# NotNightVision_r002.net
KiCad netlist of a schematic drawn in EAGLE
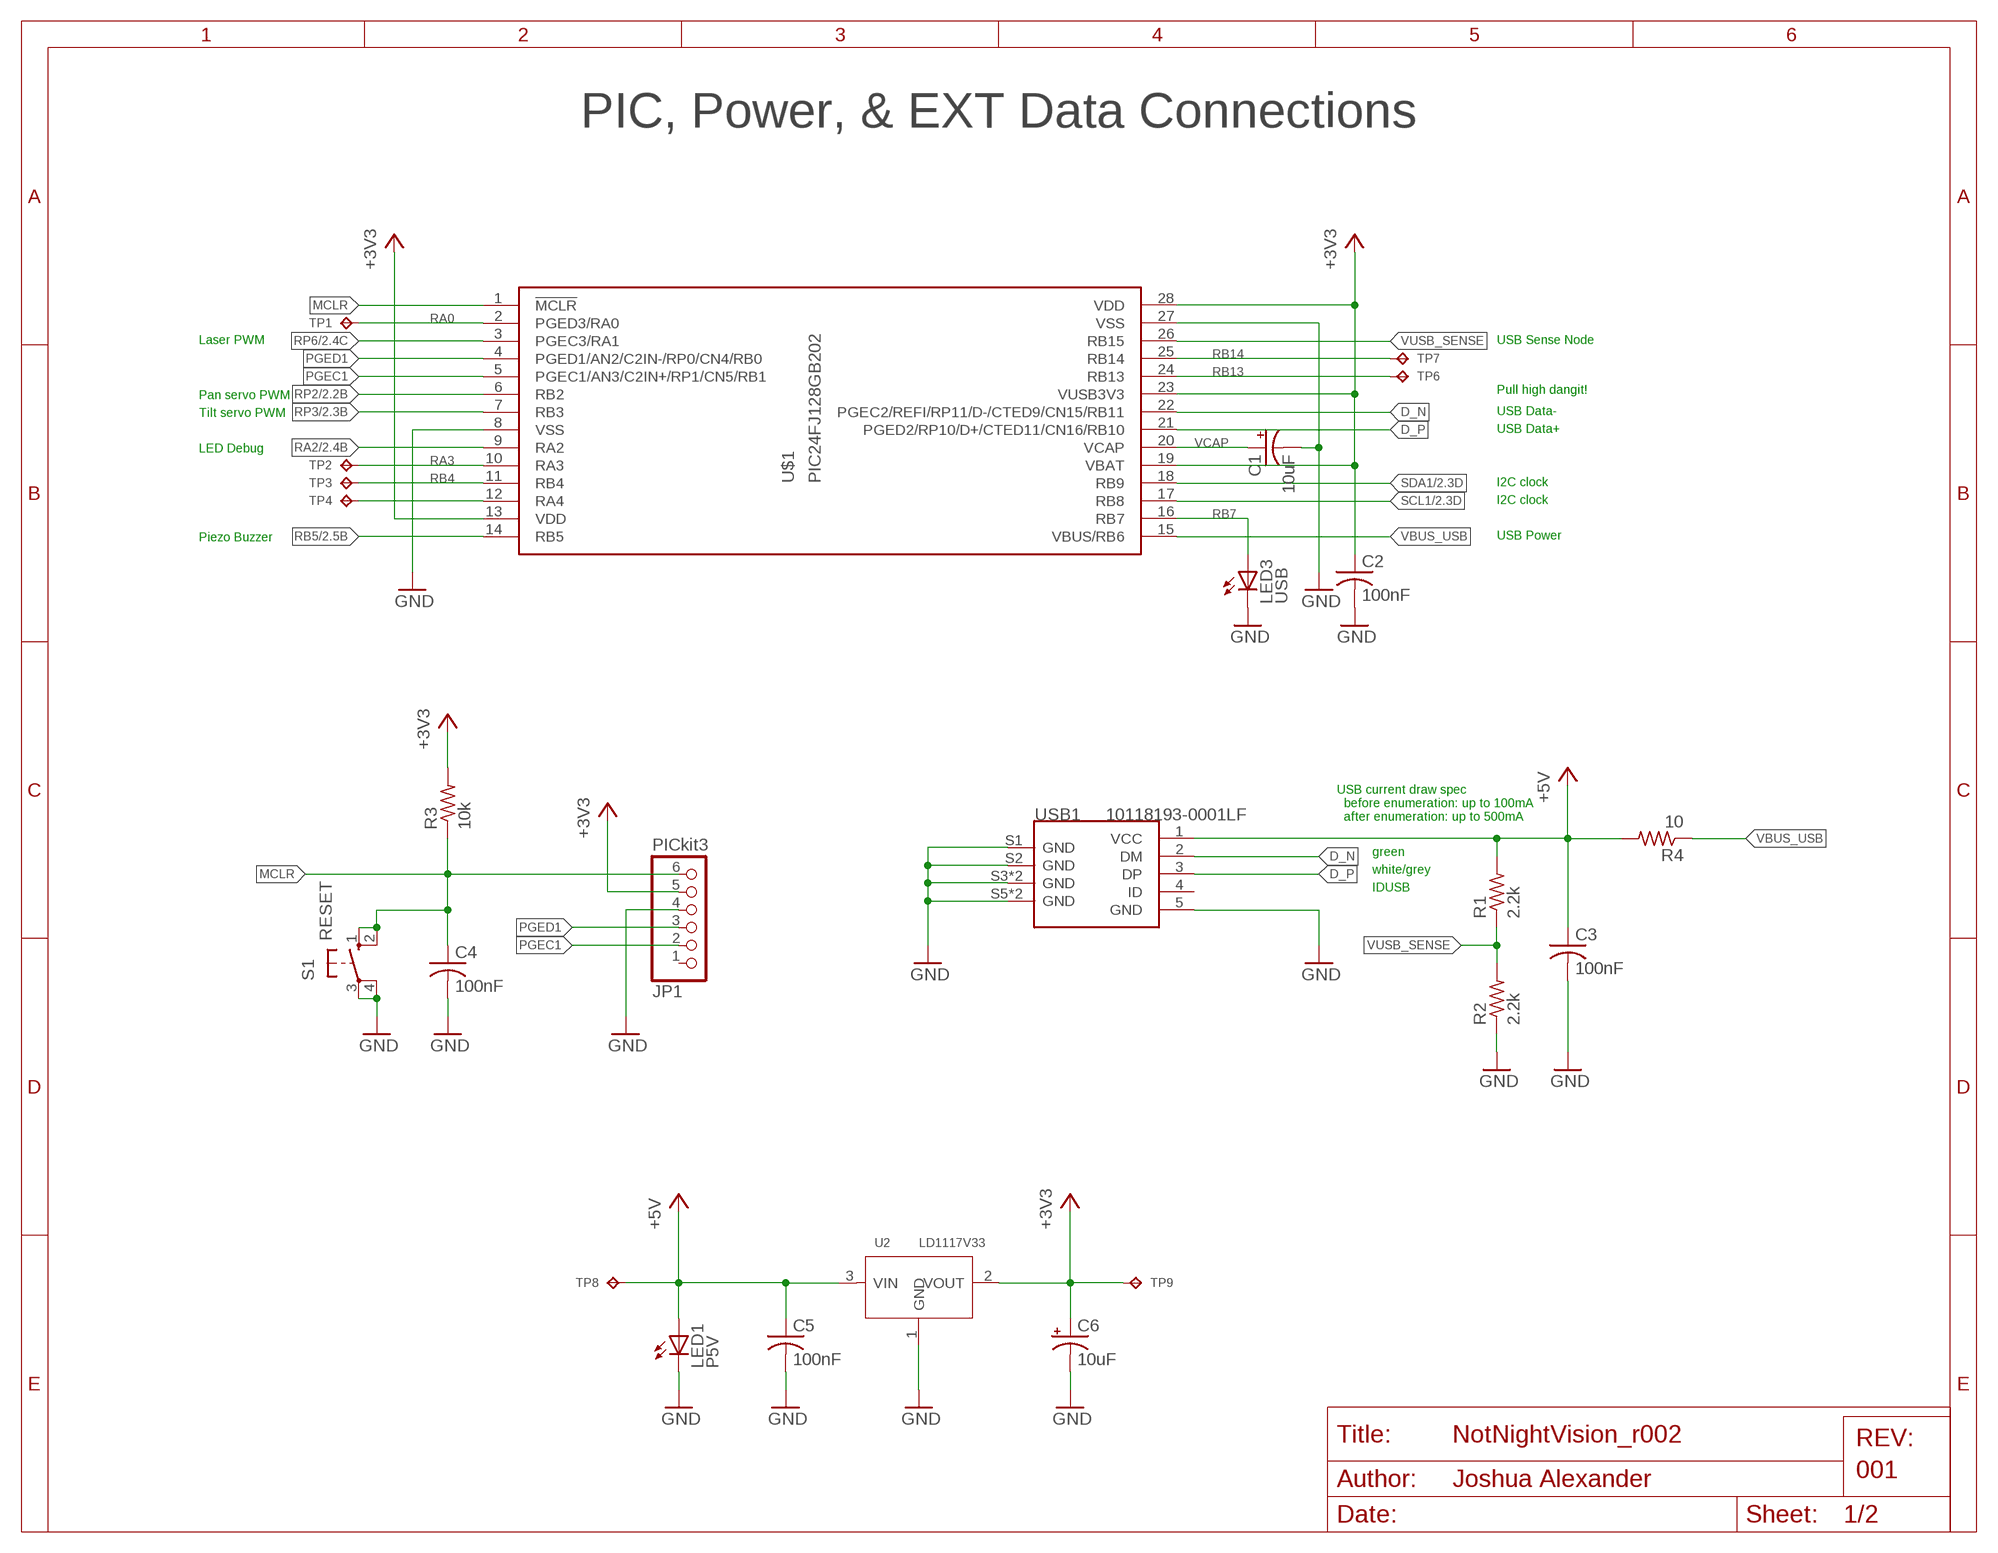
[diagram p0: schematic, sheet 1]
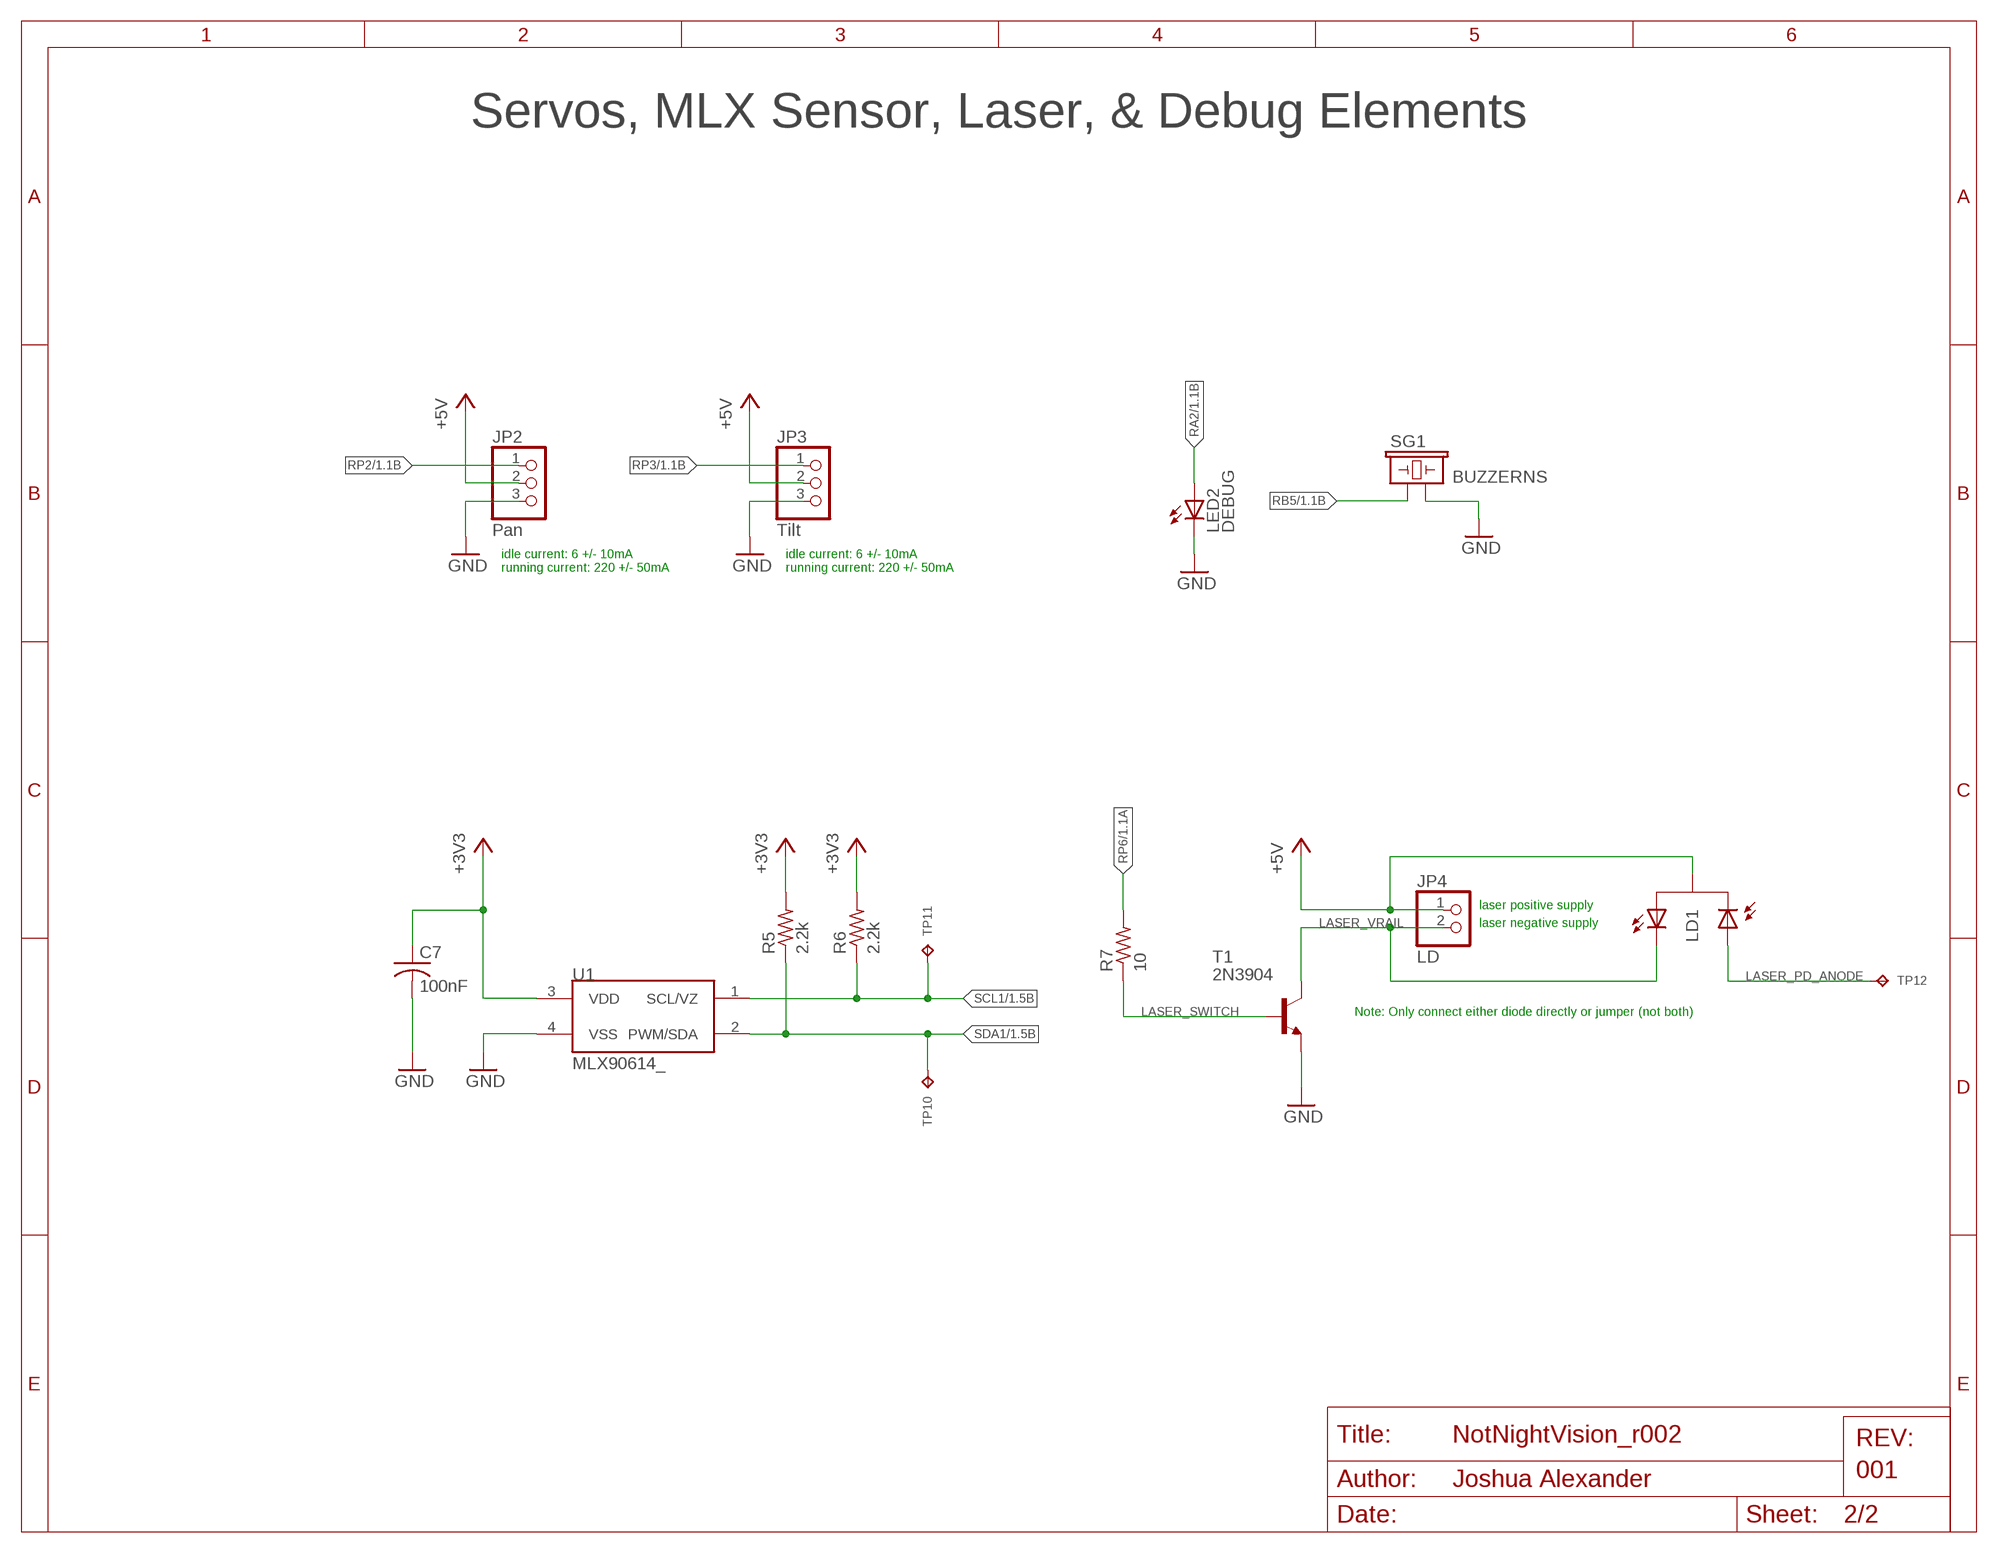
[diagram p1: schematic, sheet 2]

(export (version "E")
  (design (tool "Eeschema 10.0.6"))
  (components
    (comp (ref "C7")
      (value "100nF")
      (footprint "eagle-import:C050-030X075")
      (libsource (lib "eagle-import") (part "C-US050-030X075"))
    )
    (comp (ref "JP2")
      (value "Pan")
      (footprint "eagle-import:1X03")
      (libsource (lib "eagle-import") (part "PINHD-1X3"))
    )
    (comp (ref "JP3")
      (value "Tilt")
      (footprint "eagle-import:1X03")
      (libsource (lib "eagle-import") (part "PINHD-1X3"))
    )
    (comp (ref "JP4")
      (value "LD")
      (footprint "eagle-import:1X02")
      (libsource (lib "eagle-import") (part "PINHD-1X2"))
    )
    (comp (ref "LD1")
      (value "LASER_DIODE")
      (footprint "eagle-import:TO-18")
      (libsource (lib "eagle-import") (part "LASER_DIODE"))
    )
    (comp (ref "LED2")
      (value "DEBUG")
      (footprint "eagle-import:LED3MM")
      (libsource (lib "eagle-import") (part "LED3MM"))
    )
    (comp (ref "R5")
      (value "2.2k")
      (footprint "eagle-import:0207_7")
      (libsource (lib "eagle-import") (part "R-US_0207/7"))
    )
    (comp (ref "R6")
      (value "2.2k")
      (footprint "eagle-import:0207_7")
      (libsource (lib "eagle-import") (part "R-US_0207/7"))
    )
    (comp (ref "R7")
      (value "10")
      (footprint "eagle-import:0207_7")
      (libsource (lib "eagle-import") (part "R-US_0207/7"))
    )
    (comp (ref "SG1")
      (value "BUZZERNS")
      (footprint "eagle-import:BUZZER-12MM-NS")
      (libsource (lib "eagle-import") (part "BUZZERNS"))
    )
    (comp (ref "T1")
      (value "2N3904")
      (footprint "eagle-import:TO92")
      (libsource (lib "eagle-import") (part "2N3904"))
    )
    (comp (ref "TP10")
      (value "TP10")
      (footprint "eagle-import:10MIL_ROUND")
      (libsource (lib "eagle-import") (part "TP10"))
    )
    (comp (ref "TP11")
      (value "TP10")
      (footprint "eagle-import:10MIL_ROUND")
      (libsource (lib "eagle-import") (part "TP10"))
    )
    (comp (ref "TP12")
      (value "TP10")
      (footprint "eagle-import:10MIL_ROUND")
      (libsource (lib "eagle-import") (part "TP10"))
    )
    (comp (ref "U1")
      (value "MLX90614_")
      (footprint "eagle-import:TO-39")
      (fields (field (name "MPN") "1747"))
      (libsource (lib "eagle-import") (part "MLX90614_"))
    )
    (comp (ref "C1")
      (value "10uF")
      (footprint "eagle-import:E2,5-7")
      (libsource (lib "eagle-import") (part "CPOL-USE2.5-7"))
    )
    (comp (ref "C2")
      (value "100nF")
      (footprint "eagle-import:C050-030X075")
      (libsource (lib "eagle-import") (part "C-US050-030X075"))
    )
    (comp (ref "C3")
      (value "100nF")
      (footprint "eagle-import:C050-030X075")
      (libsource (lib "eagle-import") (part "C-US050-030X075"))
    )
    (comp (ref "C4")
      (value "100nF")
      (footprint "eagle-import:C050-030X075")
      (libsource (lib "eagle-import") (part "C-US050-030X075"))
    )
    (comp (ref "C5")
      (value "100nF")
      (footprint "eagle-import:C050-030X075")
      (libsource (lib "eagle-import") (part "C-US050-030X075"))
    )
    (comp (ref "C6")
      (value "10uF")
      (footprint "eagle-import:E2,5-7")
      (libsource (lib "eagle-import") (part "CPOL-USE2.5-7"))
    )
    (comp (ref "JP1")
      (value "PICkit3")
      (footprint "eagle-import:1X06_90")
      (libsource (lib "eagle-import") (part "PINHD-1X6/90"))
    )
    (comp (ref "LED1")
      (value "P5V")
      (footprint "eagle-import:LED5MM")
      (libsource (lib "eagle-import") (part "LED5MM"))
    )
    (comp (ref "LED3")
      (value "USB")
      (footprint "eagle-import:LED3MM")
      (libsource (lib "eagle-import") (part "LED3MM"))
    )
    (comp (ref "R1")
      (value "2.2k")
      (footprint "eagle-import:0207_7")
      (libsource (lib "eagle-import") (part "R-US_0207/7"))
    )
    (comp (ref "R2")
      (value "2.2k")
      (footprint "eagle-import:0207_7")
      (libsource (lib "eagle-import") (part "R-US_0207/7"))
    )
    (comp (ref "R3")
      (value "10k")
      (footprint "eagle-import:0207_7")
      (libsource (lib "eagle-import") (part "R-US_0207/7"))
    )
    (comp (ref "R4")
      (value "10")
      (footprint "eagle-import:0207_7")
      (libsource (lib "eagle-import") (part "R-US_0207/7"))
    )
    (comp (ref "S1")
      (value "RESET")
      (footprint "eagle-import:B3F-10XX")
      (fields (field (name "MPN") "B3F-1000"))
      (libsource (lib "eagle-import") (part "10-XX"))
    )
    (comp (ref "TP1")
      (value "TP10")
      (footprint "eagle-import:10MIL_ROUND")
      (libsource (lib "eagle-import") (part "TP10"))
    )
    (comp (ref "TP2")
      (value "TP10")
      (footprint "eagle-import:10MIL_ROUND")
      (libsource (lib "eagle-import") (part "TP10"))
    )
    (comp (ref "TP3")
      (value "TP10")
      (footprint "eagle-import:10MIL_ROUND")
      (libsource (lib "eagle-import") (part "TP10"))
    )
    (comp (ref "TP4")
      (value "TP10")
      (footprint "eagle-import:10MIL_ROUND")
      (libsource (lib "eagle-import") (part "TP10"))
    )
    (comp (ref "TP6")
      (value "TP10")
      (footprint "eagle-import:10MIL_ROUND")
      (libsource (lib "eagle-import") (part "TP10"))
    )
    (comp (ref "TP7")
      (value "TP10")
      (footprint "eagle-import:10MIL_ROUND")
      (libsource (lib "eagle-import") (part "TP10"))
    )
    (comp (ref "TP8")
      (value "TP10")
      (footprint "eagle-import:10MIL_ROUND")
      (libsource (lib "eagle-import") (part "TP10"))
    )
    (comp (ref "TP9")
      (value "TP10")
      (footprint "eagle-import:10MIL_ROUND")
      (libsource (lib "eagle-import") (part "TP10"))
    )
    (comp (ref "U$1")
      (value "PIC24FJ128GB202")
      (footprint "eagle-import:DIL28-3")
      (libsource (lib "eagle-import") (part "PIC24FJ128GB202"))
    )
    (comp (ref "U2")
      (value "LD1117V33")
      (footprint "eagle-import:TO-220V")
      (libsource (lib "eagle-import") (part "LD1117V33TO220V"))
    )
    (comp (ref "USB1")
      (value "10118193-0001LF")
      (footprint "eagle-import:MICRO-USB5+6P-SMD-0.65-B")
      (libsource (lib "eagle-import") (part "MICRO-USB-SMD-B-(10118193-0001LF)"))
    )
  )
  (nets
    (net (code "1") (name "+3V3") (class "Default")
      (node (ref "C2") (pin "1") (pinfunction "1_1") (pintype "passive"))
      (node (ref "C6") (pin "+") (pinfunction "+_+") (pintype "passive"))
      (node (ref "C7") (pin "1") (pinfunction "1_1") (pintype "passive"))
      (node (ref "JP1") (pin "5") (pinfunction "5_5") (pintype "passive"))
      (node (ref "R3") (pin "2") (pinfunction "2_2") (pintype "passive"))
      (node (ref "R5") (pin "2") (pinfunction "2_2") (pintype "passive"))
      (node (ref "R6") (pin "2") (pinfunction "2_2") (pintype "passive"))
      (node (ref "TP9") (pin "TP") (pinfunction "TP_TP") (pintype "input"))
      (node (ref "U$1") (pin "13") (pinfunction "VDD_13") (pintype "power_in"))
      (node (ref "U$1") (pin "19") (pinfunction "VBAT_19") (pintype "power_in"))
      (node (ref "U$1") (pin "23") (pinfunction "VUSB3V3_23") (pintype "bidirectional"))
      (node (ref "U$1") (pin "28") (pinfunction "VDD_28") (pintype "power_in"))
      (node (ref "U1") (pin "3") (pinfunction "VDD_3") (pintype "bidirectional"))
      (node (ref "U2") (pin "2") (pinfunction "VOUT_2") (pintype "bidirectional"))
    )
    (net (code "2") (name "+5V") (class "Default")
      (node (ref "C3") (pin "1") (pinfunction "1_1") (pintype "passive"))
      (node (ref "C5") (pin "1") (pinfunction "1_1") (pintype "passive"))
      (node (ref "JP2") (pin "2") (pinfunction "2_2") (pintype "passive"))
      (node (ref "JP3") (pin "2") (pinfunction "2_2") (pintype "passive"))
      (node (ref "JP4") (pin "1") (pinfunction "1_1") (pintype "passive"))
      (node (ref "LD1") (pin "2") (pinfunction "V_2") (pintype "passive"))
      (node (ref "LED1") (pin "A") (pinfunction "A_A") (pintype "passive"))
      (node (ref "R1") (pin "2") (pinfunction "2_2") (pintype "passive"))
      (node (ref "R4") (pin "2") (pinfunction "2_2") (pintype "passive"))
      (node (ref "TP8") (pin "TP") (pinfunction "TP_TP") (pintype "input"))
      (node (ref "U2") (pin "3") (pinfunction "VIN_3") (pintype "bidirectional"))
      (node (ref "USB1") (pin "1") (pinfunction "VCC_1") (pintype "bidirectional"))
    )
    (net (code "3") (name "D_N") (class "Default")
      (node (ref "U$1") (pin "22") (pinfunction "PGEC2/REFI/RP11/D-/CTED9/CN15/RB11_22") (pintype "bidirectional"))
      (node (ref "USB1") (pin "2") (pinfunction "DM_2") (pintype "bidirectional"))
    )
    (net (code "4") (name "D_P") (class "Default")
      (node (ref "U$1") (pin "21") (pinfunction "PGED2/RP10/D+/CTED11/CN16/RB10_21") (pintype "bidirectional"))
      (node (ref "USB1") (pin "3") (pinfunction "DP_3") (pintype "bidirectional"))
    )
    (net (code "5") (name "GND") (class "Default")
      (node (ref "C1") (pin "-") (pinfunction "-_-") (pintype "passive"))
      (node (ref "C2") (pin "2") (pinfunction "2_2") (pintype "passive"))
      (node (ref "C3") (pin "2") (pinfunction "2_2") (pintype "passive"))
      (node (ref "C4") (pin "2") (pinfunction "2_2") (pintype "passive"))
      (node (ref "C5") (pin "2") (pinfunction "2_2") (pintype "passive"))
      (node (ref "C6") (pin "-") (pinfunction "-_-") (pintype "passive"))
      (node (ref "C7") (pin "2") (pinfunction "2_2") (pintype "passive"))
      (node (ref "JP1") (pin "4") (pinfunction "4_4") (pintype "passive"))
      (node (ref "JP2") (pin "3") (pinfunction "3_3") (pintype "passive"))
      (node (ref "JP3") (pin "3") (pinfunction "3_3") (pintype "passive"))
      (node (ref "LED1") (pin "K") (pinfunction "C_K") (pintype "passive"))
      (node (ref "LED2") (pin "K") (pinfunction "C_K") (pintype "passive"))
      (node (ref "LED3") (pin "K") (pinfunction "C_K") (pintype "passive"))
      (node (ref "R2") (pin "1") (pinfunction "1_1") (pintype "passive"))
      (node (ref "S1") (pin "3") (pinfunction "P_3") (pintype "passive"))
      (node (ref "S1") (pin "4") (pinfunction "P1_4") (pintype "passive"))
      (node (ref "SG1") (pin "-") (pinfunction "2_-") (pintype "passive"))
      (node (ref "T1") (pin "3") (pinfunction "E_3") (pintype "passive"))
      (node (ref "U$1") (pin "27") (pinfunction "VSS_27") (pintype "power_in"))
      (node (ref "U$1") (pin "8") (pinfunction "VSS_8") (pintype "power_in"))
      (node (ref "U1") (pin "4") (pinfunction "VSS_4") (pintype "bidirectional"))
      (node (ref "U2") (pin "1") (pinfunction "GND_1") (pintype "bidirectional"))
      (node (ref "USB1") (pin "5") (pinfunction "GND_5") (pintype "bidirectional"))
      (node (ref "USB1") (pin "S1") (pinfunction "GND_S1") (pintype "bidirectional"))
      (node (ref "USB1") (pin "S2") (pinfunction "GND_S2") (pintype "bidirectional"))
      (node (ref "USB1") (pin "S3") (pinfunction "GND_S3") (pintype "bidirectional"))
      (node (ref "USB1") (pin "S4") (pinfunction "GND_S4") (pintype "bidirectional"))
      (node (ref "USB1") (pin "S5") (pinfunction "GND_S5") (pintype "bidirectional"))
      (node (ref "USB1") (pin "S6") (pinfunction "GND_S6") (pintype "bidirectional"))
    )
    (net (code "6") (name "LASER_PD_ANODE") (class "Default")
      (node (ref "LD1") (pin "3") (pinfunction "D+_3") (pintype "passive"))
      (node (ref "TP12") (pin "TP") (pinfunction "TP_TP") (pintype "input"))
    )
    (net (code "7") (name "LASER_SWITCH") (class "Default")
      (node (ref "R7") (pin "1") (pinfunction "1_1") (pintype "passive"))
      (node (ref "T1") (pin "2") (pinfunction "B_2") (pintype "passive"))
    )
    (net (code "8") (name "LASER_VRAIL") (class "Default")
      (node (ref "JP4") (pin "2") (pinfunction "2_2") (pintype "passive"))
      (node (ref "LD1") (pin "1") (pinfunction "D-_1") (pintype "passive"))
      (node (ref "T1") (pin "1") (pinfunction "C_1") (pintype "passive"))
    )
    (net (code "9") (name "MCLR") (class "Default")
      (node (ref "C4") (pin "1") (pinfunction "1_1") (pintype "passive"))
      (node (ref "JP1") (pin "6") (pinfunction "6_6") (pintype "passive"))
      (node (ref "R3") (pin "1") (pinfunction "1_1") (pintype "passive"))
      (node (ref "S1") (pin "1") (pinfunction "S_1") (pintype "passive"))
      (node (ref "S1") (pin "2") (pinfunction "S1_2") (pintype "passive"))
      (node (ref "U$1") (pin "1") (pinfunction "~{MCLR}_1") (pintype "bidirectional"))
    )
    (net (code "10") (name "Net-(U$1-RA4)") (class "Default")
      (node (ref "TP4") (pin "TP") (pinfunction "TP_TP") (pintype "input"))
      (node (ref "U$1") (pin "12") (pinfunction "RA4_12") (pintype "bidirectional"))
    )
    (net (code "11") (name "PGEC1") (class "Default")
      (node (ref "JP1") (pin "2") (pinfunction "2_2") (pintype "passive"))
      (node (ref "U$1") (pin "5") (pinfunction "PGEC1/AN3/C2IN+/RP1/CN5/RB1_5") (pintype "bidirectional"))
    )
    (net (code "12") (name "PGED1") (class "Default")
      (node (ref "JP1") (pin "3") (pinfunction "3_3") (pintype "passive"))
      (node (ref "U$1") (pin "4") (pinfunction "PGED1/AN2/C2IN-/RP0/CN4/RB0_4") (pintype "bidirectional"))
    )
    (net (code "13") (name "RA0") (class "Default")
      (node (ref "TP1") (pin "TP") (pinfunction "TP_TP") (pintype "input"))
      (node (ref "U$1") (pin "2") (pinfunction "PGED3/RA0_2") (pintype "bidirectional"))
    )
    (net (code "14") (name "RA2") (class "Default")
      (node (ref "LED2") (pin "A") (pinfunction "A_A") (pintype "passive"))
      (node (ref "U$1") (pin "9") (pinfunction "RA2_9") (pintype "bidirectional"))
    )
    (net (code "15") (name "RA3") (class "Default")
      (node (ref "TP2") (pin "TP") (pinfunction "TP_TP") (pintype "input"))
      (node (ref "U$1") (pin "10") (pinfunction "RA3_10") (pintype "bidirectional"))
    )
    (net (code "16") (name "RB4") (class "Default")
      (node (ref "TP3") (pin "TP") (pinfunction "TP_TP") (pintype "input"))
      (node (ref "U$1") (pin "11") (pinfunction "RB4_11") (pintype "bidirectional"))
    )
    (net (code "17") (name "RB5") (class "Default")
      (node (ref "SG1") (pin "+") (pinfunction "1_+") (pintype "passive"))
      (node (ref "U$1") (pin "14") (pinfunction "RB5_14") (pintype "bidirectional"))
    )
    (net (code "18") (name "RB7") (class "Default")
      (node (ref "LED3") (pin "A") (pinfunction "A_A") (pintype "passive"))
      (node (ref "U$1") (pin "16") (pinfunction "RB7_16") (pintype "bidirectional"))
    )
    (net (code "19") (name "RB13") (class "Default")
      (node (ref "TP6") (pin "TP") (pinfunction "TP_TP") (pintype "input"))
      (node (ref "U$1") (pin "24") (pinfunction "RB13_24") (pintype "bidirectional"))
    )
    (net (code "20") (name "RB14") (class "Default")
      (node (ref "TP7") (pin "TP") (pinfunction "TP_TP") (pintype "input"))
      (node (ref "U$1") (pin "25") (pinfunction "RB14_25") (pintype "bidirectional"))
    )
    (net (code "21") (name "RP2") (class "Default")
      (node (ref "JP2") (pin "1") (pinfunction "1_1") (pintype "passive"))
      (node (ref "U$1") (pin "6") (pinfunction "RB2_6") (pintype "bidirectional"))
    )
    (net (code "22") (name "RP3") (class "Default")
      (node (ref "JP3") (pin "1") (pinfunction "1_1") (pintype "passive"))
      (node (ref "U$1") (pin "7") (pinfunction "RB3_7") (pintype "bidirectional"))
    )
    (net (code "23") (name "RP6") (class "Default")
      (node (ref "R7") (pin "2") (pinfunction "2_2") (pintype "passive"))
      (node (ref "U$1") (pin "3") (pinfunction "PGEC3/RA1_3") (pintype "bidirectional"))
    )
    (net (code "24") (name "SCL1") (class "Default")
      (node (ref "R6") (pin "1") (pinfunction "1_1") (pintype "passive"))
      (node (ref "TP11") (pin "TP") (pinfunction "TP_TP") (pintype "input"))
      (node (ref "U$1") (pin "17") (pinfunction "RB8_17") (pintype "bidirectional"))
      (node (ref "U1") (pin "1") (pinfunction "SCL/VZ_1") (pintype "bidirectional"))
    )
    (net (code "25") (name "SDA1") (class "Default")
      (node (ref "R5") (pin "1") (pinfunction "1_1") (pintype "passive"))
      (node (ref "TP10") (pin "TP") (pinfunction "TP_TP") (pintype "input"))
      (node (ref "U$1") (pin "18") (pinfunction "RB9_18") (pintype "bidirectional"))
      (node (ref "U1") (pin "2") (pinfunction "PWM/SDA_2") (pintype "bidirectional"))
    )
    (net (code "26") (name "VBUS_USB") (class "Default")
      (node (ref "R4") (pin "1") (pinfunction "1_1") (pintype "passive"))
      (node (ref "U$1") (pin "15") (pinfunction "VBUS/RB6_15") (pintype "power_in"))
    )
    (net (code "27") (name "VCAP") (class "Default")
      (node (ref "C1") (pin "+") (pinfunction "+_+") (pintype "passive"))
      (node (ref "U$1") (pin "20") (pinfunction "VCAP_20") (pintype "passive"))
    )
    (net (code "28") (name "VUSB_SENSE") (class "Default")
      (node (ref "R1") (pin "1") (pinfunction "1_1") (pintype "passive"))
      (node (ref "R2") (pin "2") (pinfunction "2_2") (pintype "passive"))
      (node (ref "U$1") (pin "26") (pinfunction "RB15_26") (pintype "bidirectional"))
    )
    (net (code "29") (name "unconnected-(JP1-Pad1)") (class "Default")
      (node (ref "JP1") (pin "1") (pinfunction "1_1") (pintype "passive"))
    )
    (net (code "30") (name "unconnected-(USB1-ID-Pad4)") (class "Default")
      (node (ref "USB1") (pin "4") (pinfunction "ID_4") (pintype "bidirectional"))
    )
  )
)
